# MF-CI_4_2-SDW_-_EXTERNAL.net
KiCad netlist of a schematic drawn in Altium Designer
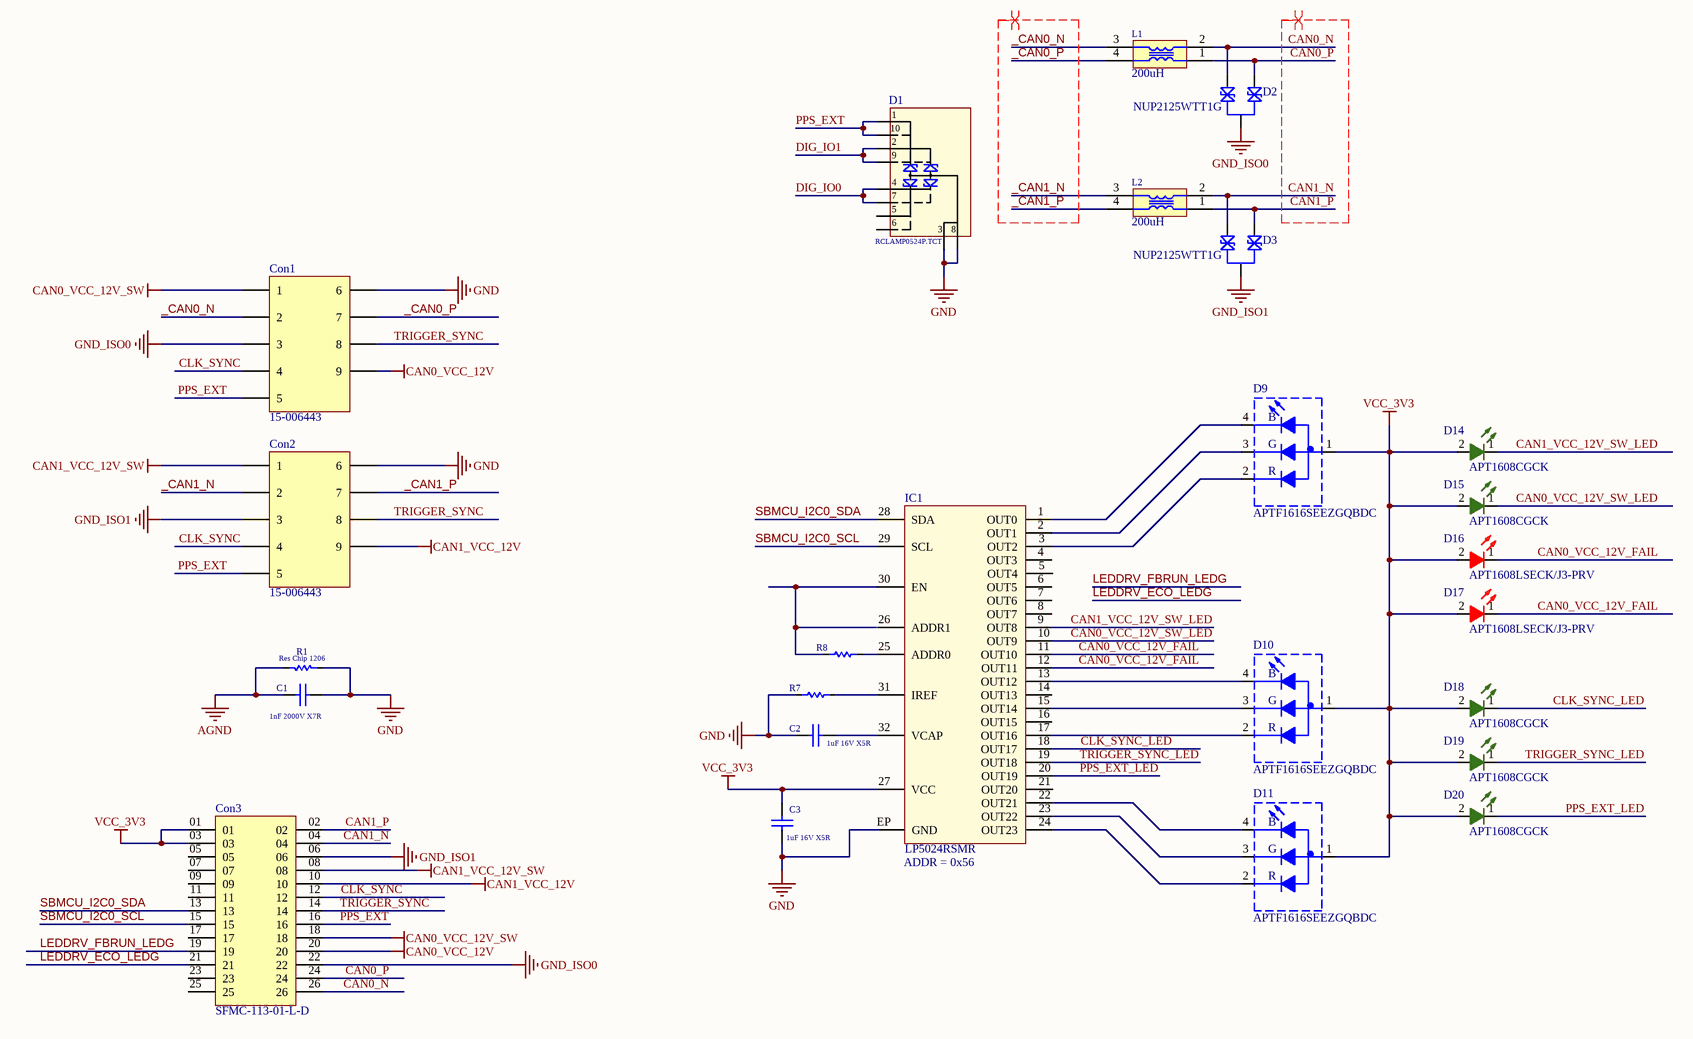
[diagram p0: MF-CI.4.2-SDW - EXTERNAL.SchDoc]

(export (version "E")
  (design (tool "Eeschema 10.0.6"))
  (components
    (comp (ref "C1")
      (value "1nF 2000V X7R")
      (footprint "1206")
      (description "Cap Chip 1nF 2000V X7R 1206")
      (libsource (lib "BBDAQ") (part "Cap"))
    )
    (comp (ref "C2")
      (value "1uF 16V X5R")
      (footprint "0402")
      (description "Capacitor, 1u, 16V, 10%, X5R, 0402")
      (libsource (lib "BBDAQ") (part "CC0402KRX5R7BB105"))
    )
    (comp (ref "C3")
      (value "1uF 16V X5R")
      (footprint "0402")
      (description "Capacitor, 1u, 16V, 10%, X5R, 0402")
      (libsource (lib "BBDAQ") (part "CC0402KRX5R7BB105"))
    )
    (comp (ref "Con1")
      (value "15-006443")
      (footprint "DSUB-9 Male D, 2.74")
      (description "Conn, D-Sub, Male, 9, 2mm, Str, -40/+105")
      (libsource (lib "BBDAQ") (part "15-006443"))
    )
    (comp (ref "Con2")
      (value "15-006443")
      (footprint "DSUB-9 Male D, 2.74")
      (description "Conn, D-Sub, Male, 9, 2mm, Str, -40/+105")
      (libsource (lib "BBDAQ") (part "15-006443"))
    )
    (comp (ref "Con3")
      (value "SFMC-113-01-L-D")
      (footprint "SAMTEC_SFMC-113-01-L-D")
      (description "Conn, Receptacle, Female, 13x2, 1.27mm, Vertical, -55/+125")
      (libsource (lib "BBDAQ") (part "SFMC-113-01-L-D"))
    )
    (comp (ref "D1")
      (value "RCLAMP0524P.TCT")
      (footprint "SLP2510P8")
      (description "Diode array TVS, RCLAMP0524P.TCT")
      (libsource (lib "BBDAQ") (part "CMP-SEM-000069"))
    )
    (comp (ref "D2")
      (value "NUP2125WTT1G")
      (footprint "SOT323-3L(SC-70)")
      (description "Diode dual TVS, SOT323, bidrectional, CAN-FD")
      (libsource (lib "BBDAQ") (part "dual_TVS_diode"))
    )
    (comp (ref "D3")
      (value "NUP2125WTT1G")
      (footprint "SOT323-3L(SC-70)")
      (description "Diode dual TVS, SOT323, bidrectional, CAN-FD")
      (libsource (lib "BBDAQ") (part "dual_TVS_diode"))
    )
    (comp (ref "D9")
      (value "APTF1616SEEZGQBDC")
      (footprint "KINGBRIGHT_APTF1616SEEZGQBDC")
      (description "Diode, LED, Red/Green/Blue, 5V, 20mA, -40/+85")
      (libsource (lib "BBDAQ") (part "APTF1616SEEZGQBDC"))
    )
    (comp (ref "D10")
      (value "APTF1616SEEZGQBDC")
      (footprint "KINGBRIGHT_APTF1616SEEZGQBDC")
      (description "Diode, LED, Red/Green/Blue, 5V, 20mA, -40/+85")
      (libsource (lib "BBDAQ") (part "APTF1616SEEZGQBDC"))
    )
    (comp (ref "D11")
      (value "APTF1616SEEZGQBDC")
      (footprint "KINGBRIGHT_APTF1616SEEZGQBDC")
      (description "Diode, LED, Red/Green/Blue, 5V, 20mA, -40/+85")
      (libsource (lib "BBDAQ") (part "APTF1616SEEZGQBDC"))
    )
    (comp (ref "D14")
      (value "APT1608CGCK")
      (footprint "APT1608CGCK")
      (description "Diode, LED, Green, 5V, 20mA, Vertical, -40/+85, 0603")
      (libsource (lib "BBDAQ") (part "APT1608CGCK"))
    )
    (comp (ref "D15")
      (value "APT1608CGCK")
      (footprint "APT1608CGCK")
      (description "Diode, LED, Green, 5V, 20mA, Vertical, -40/+85, 0603")
      (libsource (lib "BBDAQ") (part "APT1608CGCK"))
    )
    (comp (ref "D16")
      (value "APT1608LSECK/J3-PRV")
      (footprint "Kingbright_APT1608LSECK/J3-PRV")
      (description "Diode, LED, Red, 5V, 20mA, -40/+85")
      (libsource (lib "BBDAQ") (part "APT1608LSECK/J3-PRV"))
    )
    (comp (ref "D17")
      (value "APT1608LSECK/J3-PRV")
      (footprint "Kingbright_APT1608LSECK/J3-PRV")
      (description "Diode, LED, Red, 5V, 20mA, -40/+85")
      (libsource (lib "BBDAQ") (part "APT1608LSECK/J3-PRV"))
    )
    (comp (ref "D18")
      (value "APT1608CGCK")
      (footprint "APT1608CGCK")
      (description "Diode, LED, Green, 5V, 20mA, Vertical, -40/+85, 0603")
      (libsource (lib "BBDAQ") (part "APT1608CGCK"))
    )
    (comp (ref "D19")
      (value "APT1608CGCK")
      (footprint "APT1608CGCK")
      (description "Diode, LED, Green, 5V, 20mA, Vertical, -40/+85, 0603")
      (libsource (lib "BBDAQ") (part "APT1608CGCK"))
    )
    (comp (ref "D20")
      (value "APT1608CGCK")
      (footprint "APT1608CGCK")
      (description "Diode, LED, Green, 5V, 20mA, Vertical, -40/+85, 0603")
      (libsource (lib "BBDAQ") (part "APT1608CGCK"))
    )
    (comp (ref "IC1")
      (value "LP5024RSMR")
      (footprint "QFN-32[8x8]_0,25/0,50_5x5x1_HD[2,10x2,10]")
      (description "IC, LED Driver, 24 LEDs, 2.7-5.5V, 35mA, -40/+85, VFQFN-32")
      (fields (field (name "MANUFACTURER") "TI"))
      (libsource (lib "BBDAQ") (part "LP5024RSMR"))
    )
    (comp (ref "L1")
      (value "200uH")
      (footprint "ACT1210L")
      (description "ACT1210L-201-2P-TL00 -  Filter Common Mode ACT1210L Series 200uH 70mA 2.5mm x 3.9mm x 2.5mm")
      (libsource (lib "BBDAQ") (part "CM_Choke"))
    )
    (comp (ref "L2")
      (value "200uH")
      (footprint "ACT1210L")
      (description "ACT1210L-201-2P-TL00 -  Filter Common Mode ACT1210L Series 200uH 70mA 2.5mm x 3.9mm x 2.5mm")
      (libsource (lib "BBDAQ") (part "CM_Choke"))
    )
    (comp (ref "R1")
      (value "Res Chip 1206")
      (footprint "1206")
      (libsource (lib "BBDAQ") (part "CMP-RST-001901"))
    )
    (comp (ref "R7")
      (value "Res Chip 0402")
      (footprint "0402")
      (libsource (lib "BBDAQ") (part "CMP-RST-001998"))
    )
    (comp (ref "R8")
      (value "Res Chip 0402")
      (footprint "0402")
      (libsource (lib "BBDAQ") (part "CMP-RST-001998"))
    )
  )
  (nets
    (net (code "1") (name "/CAN0_N") (class "Default")
      (node (ref "Con3") (pin "26") (pinfunction "26_26") (pintype "passive"))
      (node (ref "D2") (pin "1") (pinfunction "1_1") (pintype "passive"))
      (node (ref "L1") (pin "2") (pintype "passive"))
    )
    (net (code "2") (name "/CAN0_P") (class "Default")
      (node (ref "Con3") (pin "24") (pinfunction "24_24") (pintype "passive"))
      (node (ref "D2") (pin "2") (pinfunction "2_2") (pintype "passive"))
      (node (ref "L1") (pin "1") (pintype "passive"))
    )
    (net (code "3") (name "/CAN0_VCC_12V_FAIL") (class "Default")
      (node (ref "D16") (pin "1") (pinfunction "K_1") (pintype "passive"))
      (node (ref "D17") (pin "1") (pinfunction "K_1") (pintype "passive"))
      (node (ref "IC1") (pin "11") (pinfunction "OUT10_11") (pintype "passive"))
      (node (ref "IC1") (pin "12") (pinfunction "OUT11_12") (pintype "passive"))
    )
    (net (code "4") (name "/CAN0_VCC_12V_SW_LED") (class "Default")
      (node (ref "D15") (pin "1") (pinfunction "K_1") (pintype "passive"))
      (node (ref "IC1") (pin "10") (pinfunction "OUT9_10") (pintype "passive"))
    )
    (net (code "5") (name "/CAN1_N") (class "Default")
      (node (ref "Con3") (pin "04") (pinfunction "04_04") (pintype "passive"))
      (node (ref "D3") (pin "1") (pinfunction "1_1") (pintype "passive"))
      (node (ref "L2") (pin "2") (pintype "passive"))
    )
    (net (code "6") (name "/CAN1_P") (class "Default")
      (node (ref "Con3") (pin "02") (pinfunction "02_02") (pintype "passive"))
      (node (ref "D3") (pin "2") (pinfunction "2_2") (pintype "passive"))
      (node (ref "L2") (pin "1") (pintype "passive"))
    )
    (net (code "7") (name "/CAN1_VCC_12V_SW_LED") (class "Default")
      (node (ref "D14") (pin "1") (pinfunction "K_1") (pintype "passive"))
      (node (ref "IC1") (pin "9") (pinfunction "OUT8_9") (pintype "passive"))
    )
    (net (code "8") (name "/CLK_SYNC") (class "Default")
      (node (ref "Con1") (pin "4") (pinfunction "4_4") (pintype "passive"))
      (node (ref "Con2") (pin "4") (pinfunction "4_4") (pintype "passive"))
      (node (ref "Con3") (pin "12") (pinfunction "12_12") (pintype "passive"))
    )
    (net (code "9") (name "/CLK_SYNC_LED") (class "Default")
      (node (ref "D18") (pin "1") (pinfunction "K_1") (pintype "passive"))
      (node (ref "IC1") (pin "18") (pinfunction "OUT17_18") (pintype "passive"))
    )
    (net (code "10") (name "/DIG_IO0") (class "Default")
      (node (ref "D1") (pin "4") (pinfunction "4_4") (pintype "passive"))
      (node (ref "D1") (pin "7") (pinfunction "7_7") (pintype "passive"))
    )
    (net (code "11") (name "/DIG_IO1") (class "Default")
      (node (ref "D1") (pin "2") (pinfunction "2_2") (pintype "passive"))
      (node (ref "D1") (pin "9") (pinfunction "9_9") (pintype "passive"))
    )
    (net (code "12") (name "/LEDDRV_ECO_LEDG") (class "Default")
      (node (ref "Con3") (pin "21") (pinfunction "21_21") (pintype "passive"))
    )
    (net (code "13") (name "/LEDDRV_FBRUN_LEDG") (class "Default")
      (node (ref "Con3") (pin "19") (pinfunction "19_19") (pintype "passive"))
    )
    (net (code "14") (name "/PPS_EXT") (class "Default")
      (node (ref "Con1") (pin "5") (pinfunction "5_5") (pintype "passive"))
      (node (ref "Con2") (pin "5") (pinfunction "5_5") (pintype "passive"))
      (node (ref "Con3") (pin "16") (pinfunction "16_16") (pintype "passive"))
      (node (ref "D1") (pin "1") (pinfunction "1_1") (pintype "passive"))
      (node (ref "D1") (pin "10") (pinfunction "10_10") (pintype "passive"))
    )
    (net (code "15") (name "/PPS_EXT_LED") (class "Default")
      (node (ref "D20") (pin "1") (pinfunction "K_1") (pintype "passive"))
      (node (ref "IC1") (pin "20") (pinfunction "OUT19_20") (pintype "passive"))
    )
    (net (code "16") (name "/SBMCU_I2C0_SCL") (class "Default")
      (node (ref "Con3") (pin "15") (pinfunction "15_15") (pintype "passive"))
      (node (ref "IC1") (pin "29") (pinfunction "SCL_29") (pintype "passive"))
    )
    (net (code "17") (name "/SBMCU_I2C0_SDA") (class "Default")
      (node (ref "Con3") (pin "13") (pinfunction "13_13") (pintype "passive"))
      (node (ref "IC1") (pin "28") (pinfunction "SDA_28") (pintype "passive"))
    )
    (net (code "18") (name "/TRIGGER_SYNC") (class "Default")
      (node (ref "Con1") (pin "8") (pinfunction "8_8") (pintype "passive"))
      (node (ref "Con2") (pin "8") (pinfunction "8_8") (pintype "passive"))
      (node (ref "Con3") (pin "14") (pinfunction "14_14") (pintype "passive"))
    )
    (net (code "19") (name "/TRIGGER_SYNC_LED") (class "Default")
      (node (ref "D19") (pin "1") (pinfunction "K_1") (pintype "passive"))
      (node (ref "IC1") (pin "19") (pinfunction "OUT18_19") (pintype "passive"))
    )
    (net (code "20") (name "/_CAN0_N") (class "Default")
      (node (ref "Con1") (pin "2") (pinfunction "2_2") (pintype "passive"))
      (node (ref "L1") (pin "3") (pintype "passive"))
    )
    (net (code "21") (name "/_CAN0_P") (class "Default")
      (node (ref "Con1") (pin "7") (pinfunction "7_7") (pintype "passive"))
      (node (ref "L1") (pin "4") (pintype "passive"))
    )
    (net (code "22") (name "/_CAN1_N") (class "Default")
      (node (ref "Con2") (pin "2") (pinfunction "2_2") (pintype "passive"))
      (node (ref "L2") (pin "3") (pintype "passive"))
    )
    (net (code "23") (name "/_CAN1_P") (class "Default")
      (node (ref "Con2") (pin "7") (pinfunction "7_7") (pintype "passive"))
      (node (ref "L2") (pin "4") (pintype "passive"))
    )
    (net (code "24") (name "AGND") (class "Default")
      (node (ref "C1") (pin "1") (pinfunction "1_1") (pintype "passive"))
      (node (ref "R1") (pin "2") (pinfunction "2_2") (pintype "passive"))
    )
    (net (code "25") (name "CAN0_VCC_12V") (class "Default")
      (node (ref "Con1") (pin "9") (pinfunction "9_9") (pintype "passive"))
      (node (ref "Con3") (pin "20") (pinfunction "20_20") (pintype "passive"))
    )
    (net (code "26") (name "CAN0_VCC_12V_SW") (class "Default")
      (node (ref "Con1") (pin "1") (pinfunction "1_1") (pintype "passive"))
      (node (ref "Con3") (pin "18") (pinfunction "18_18") (pintype "passive"))
    )
    (net (code "27") (name "CAN1_VCC_12V") (class "Default")
      (node (ref "Con2") (pin "9") (pinfunction "9_9") (pintype "passive"))
      (node (ref "Con3") (pin "10") (pinfunction "10_10") (pintype "passive"))
    )
    (net (code "28") (name "CAN1_VCC_12V_SW") (class "Default")
      (node (ref "Con2") (pin "1") (pinfunction "1_1") (pintype "passive"))
      (node (ref "Con3") (pin "08") (pinfunction "08_08") (pintype "passive"))
    )
    (net (code "29") (name "GND") (class "Default")
      (node (ref "C1") (pin "2") (pinfunction "2_2") (pintype "passive"))
      (node (ref "C2") (pin "2") (pinfunction "2_2") (pintype "passive"))
      (node (ref "C3") (pin "1") (pinfunction "1_1") (pintype "passive"))
      (node (ref "Con1") (pin "6") (pinfunction "6_6") (pintype "passive"))
      (node (ref "Con2") (pin "6") (pinfunction "6_6") (pintype "passive"))
      (node (ref "D1") (pin "3") (pinfunction "3_3") (pintype "passive"))
      (node (ref "D1") (pin "8") (pinfunction "8_8") (pintype "passive"))
      (node (ref "IC1") (pin "EP") (pinfunction "GND_EP") (pintype "passive"))
      (node (ref "R1") (pin "1") (pinfunction "1_1") (pintype "passive"))
      (node (ref "R7") (pin "2") (pinfunction "2_2") (pintype "passive"))
    )
    (net (code "30") (name "GND_ISO0") (class "Default")
      (node (ref "Con1") (pin "3") (pinfunction "3_3") (pintype "passive"))
      (node (ref "Con3") (pin "22") (pinfunction "22_22") (pintype "passive"))
      (node (ref "D2") (pin "3") (pinfunction "3_3") (pintype "passive"))
    )
    (net (code "31") (name "GND_ISO1") (class "Default")
      (node (ref "Con2") (pin "3") (pinfunction "3_3") (pintype "passive"))
      (node (ref "Con3") (pin "06") (pinfunction "06_06") (pintype "passive"))
      (node (ref "D3") (pin "3") (pinfunction "3_3") (pintype "passive"))
    )
    (net (code "32") (name "Net-(IC1-ADDR0)") (class "Default")
      (node (ref "IC1") (pin "25") (pinfunction "ADDR0_25") (pintype "passive"))
      (node (ref "R8") (pin "2") (pinfunction "2_2") (pintype "passive"))
    )
    (net (code "33") (name "Net-(IC1-EN)") (class "Default")
      (node (ref "IC1") (pin "30") (pinfunction "EN_30") (pintype "passive"))
      (node (ref "R8") (pin "1") (pinfunction "1_1") (pintype "passive"))
    )
    (net (code "34") (name "Net-(IC1-IREF)") (class "Default")
      (node (ref "IC1") (pin "31") (pinfunction "IREF_31") (pintype "passive"))
      (node (ref "R7") (pin "1") (pinfunction "1_1") (pintype "passive"))
    )
    (net (code "35") (name "Net-(IC1-OUT0)") (class "Default")
      (node (ref "D9") (pin "4") (pinfunction "K_4") (pintype "passive"))
      (node (ref "IC1") (pin "1") (pinfunction "OUT0_1") (pintype "passive"))
    )
    (net (code "36") (name "Net-(IC1-OUT1)") (class "Default")
      (node (ref "D9") (pin "3") (pinfunction "K_3") (pintype "passive"))
      (node (ref "IC1") (pin "2") (pinfunction "OUT1_2") (pintype "passive"))
    )
    (net (code "37") (name "Net-(IC1-OUT2)") (class "Default")
      (node (ref "D9") (pin "2") (pinfunction "K_2") (pintype "passive"))
      (node (ref "IC1") (pin "3") (pinfunction "OUT2_3") (pintype "passive"))
    )
    (net (code "38") (name "Net-(IC1-OUT12)") (class "Default")
      (node (ref "D10") (pin "4") (pinfunction "K_4") (pintype "passive"))
      (node (ref "IC1") (pin "13") (pinfunction "OUT12_13") (pintype "passive"))
    )
    (net (code "39") (name "Net-(IC1-OUT14)") (class "Default")
      (node (ref "D10") (pin "3") (pinfunction "K_3") (pintype "passive"))
      (node (ref "IC1") (pin "15") (pinfunction "OUT14_15") (pintype "passive"))
    )
    (net (code "40") (name "Net-(IC1-OUT16)") (class "Default")
      (node (ref "D10") (pin "2") (pinfunction "K_2") (pintype "passive"))
      (node (ref "IC1") (pin "17") (pinfunction "OUT16_17") (pintype "passive"))
    )
    (net (code "41") (name "Net-(IC1-OUT21)") (class "Default")
      (node (ref "D11") (pin "4") (pinfunction "K_4") (pintype "passive"))
      (node (ref "IC1") (pin "22") (pinfunction "OUT21_22") (pintype "passive"))
    )
    (net (code "42") (name "Net-(IC1-OUT22)") (class "Default")
      (node (ref "D11") (pin "3") (pinfunction "K_3") (pintype "passive"))
      (node (ref "IC1") (pin "23") (pinfunction "OUT22_23") (pintype "passive"))
    )
    (net (code "43") (name "Net-(IC1-OUT23)") (class "Default")
      (node (ref "D11") (pin "2") (pinfunction "K_2") (pintype "passive"))
      (node (ref "IC1") (pin "24") (pinfunction "OUT23_24") (pintype "passive"))
    )
    (net (code "44") (name "Net-(IC1-VCAP)") (class "Default")
      (node (ref "C2") (pin "1") (pinfunction "1_1") (pintype "passive"))
      (node (ref "IC1") (pin "32") (pinfunction "VCAP_32") (pintype "passive"))
    )
    (net (code "45") (name "VCC_3V3") (class "Default")
      (node (ref "C3") (pin "2") (pinfunction "2_2") (pintype "passive"))
      (node (ref "Con3") (pin "01") (pinfunction "01_01") (pintype "passive"))
      (node (ref "Con3") (pin "03") (pinfunction "03_03") (pintype "passive"))
      (node (ref "D10") (pin "1") (pinfunction "A_1") (pintype "passive"))
      (node (ref "D11") (pin "1") (pinfunction "A_1") (pintype "passive"))
      (node (ref "D14") (pin "2") (pinfunction "A_2") (pintype "passive"))
      (node (ref "D15") (pin "2") (pinfunction "A_2") (pintype "passive"))
      (node (ref "D16") (pin "2") (pinfunction "A_2") (pintype "passive"))
      (node (ref "D17") (pin "2") (pinfunction "A_2") (pintype "passive"))
      (node (ref "D18") (pin "2") (pinfunction "A_2") (pintype "passive"))
      (node (ref "D19") (pin "2") (pinfunction "A_2") (pintype "passive"))
      (node (ref "D20") (pin "2") (pinfunction "A_2") (pintype "passive"))
      (node (ref "D9") (pin "1") (pinfunction "A_1") (pintype "passive"))
      (node (ref "IC1") (pin "27") (pinfunction "VCC_27") (pintype "passive"))
    )
    (net (code "46") (name "unconnected-(Con3-Pad05)") (class "Default")
      (node (ref "Con3") (pin "05") (pinfunction "05_05") (pintype "passive"))
    )
    (net (code "47") (name "unconnected-(Con3-Pad07)") (class "Default")
      (node (ref "Con3") (pin "07") (pinfunction "07_07") (pintype "passive"))
    )
    (net (code "48") (name "unconnected-(Con3-Pad09)") (class "Default")
      (node (ref "Con3") (pin "09") (pinfunction "09_09") (pintype "passive"))
    )
    (net (code "49") (name "unconnected-(Con3-Pad11)") (class "Default")
      (node (ref "Con3") (pin "11") (pinfunction "11_11") (pintype "passive"))
    )
    (net (code "50") (name "unconnected-(Con3-Pad17)") (class "Default")
      (node (ref "Con3") (pin "17") (pinfunction "17_17") (pintype "passive"))
    )
    (net (code "51") (name "unconnected-(Con3-Pad23)") (class "Default")
      (node (ref "Con3") (pin "23") (pinfunction "23_23") (pintype "passive"))
    )
    (net (code "52") (name "unconnected-(Con3-Pad25)") (class "Default")
      (node (ref "Con3") (pin "25") (pinfunction "25_25") (pintype "passive"))
    )
    (net (code "53") (name "unconnected-(D1-Pad5)") (class "Default")
      (node (ref "D1") (pin "5") (pinfunction "5_5") (pintype "passive"))
    )
    (net (code "54") (name "unconnected-(D1-Pad6)") (class "Default")
      (node (ref "D1") (pin "6") (pinfunction "6_6") (pintype "passive"))
    )
    (net (code "55") (name "unconnected-(IC1-ADDR1-Pad26)") (class "Default")
      (node (ref "IC1") (pin "26") (pinfunction "ADDR1_26") (pintype "passive"))
    )
    (net (code "56") (name "unconnected-(IC1-OUT3-Pad4)") (class "Default")
      (node (ref "IC1") (pin "4") (pinfunction "OUT3_4") (pintype "passive"))
    )
    (net (code "57") (name "unconnected-(IC1-OUT4-Pad5)") (class "Default")
      (node (ref "IC1") (pin "5") (pinfunction "OUT4_5") (pintype "passive"))
    )
    (net (code "58") (name "unconnected-(IC1-OUT5-Pad6)") (class "Default")
      (node (ref "IC1") (pin "6") (pinfunction "OUT5_6") (pintype "passive"))
    )
    (net (code "59") (name "unconnected-(IC1-OUT6-Pad7)") (class "Default")
      (node (ref "IC1") (pin "7") (pinfunction "OUT6_7") (pintype "passive"))
    )
    (net (code "60") (name "unconnected-(IC1-OUT7-Pad8)") (class "Default")
      (node (ref "IC1") (pin "8") (pinfunction "OUT7_8") (pintype "passive"))
    )
    (net (code "61") (name "unconnected-(IC1-OUT13-Pad14)") (class "Default")
      (node (ref "IC1") (pin "14") (pinfunction "OUT13_14") (pintype "passive"))
    )
    (net (code "62") (name "unconnected-(IC1-OUT15-Pad16)") (class "Default")
      (node (ref "IC1") (pin "16") (pinfunction "OUT15_16") (pintype "passive"))
    )
    (net (code "63") (name "unconnected-(IC1-OUT20-Pad21)") (class "Default")
      (node (ref "IC1") (pin "21") (pinfunction "OUT20_21") (pintype "passive"))
    )
  )
)
